# unicorder-temp-mk-2_2.net
KiCad netlist of a schematic drawn in EAGLE
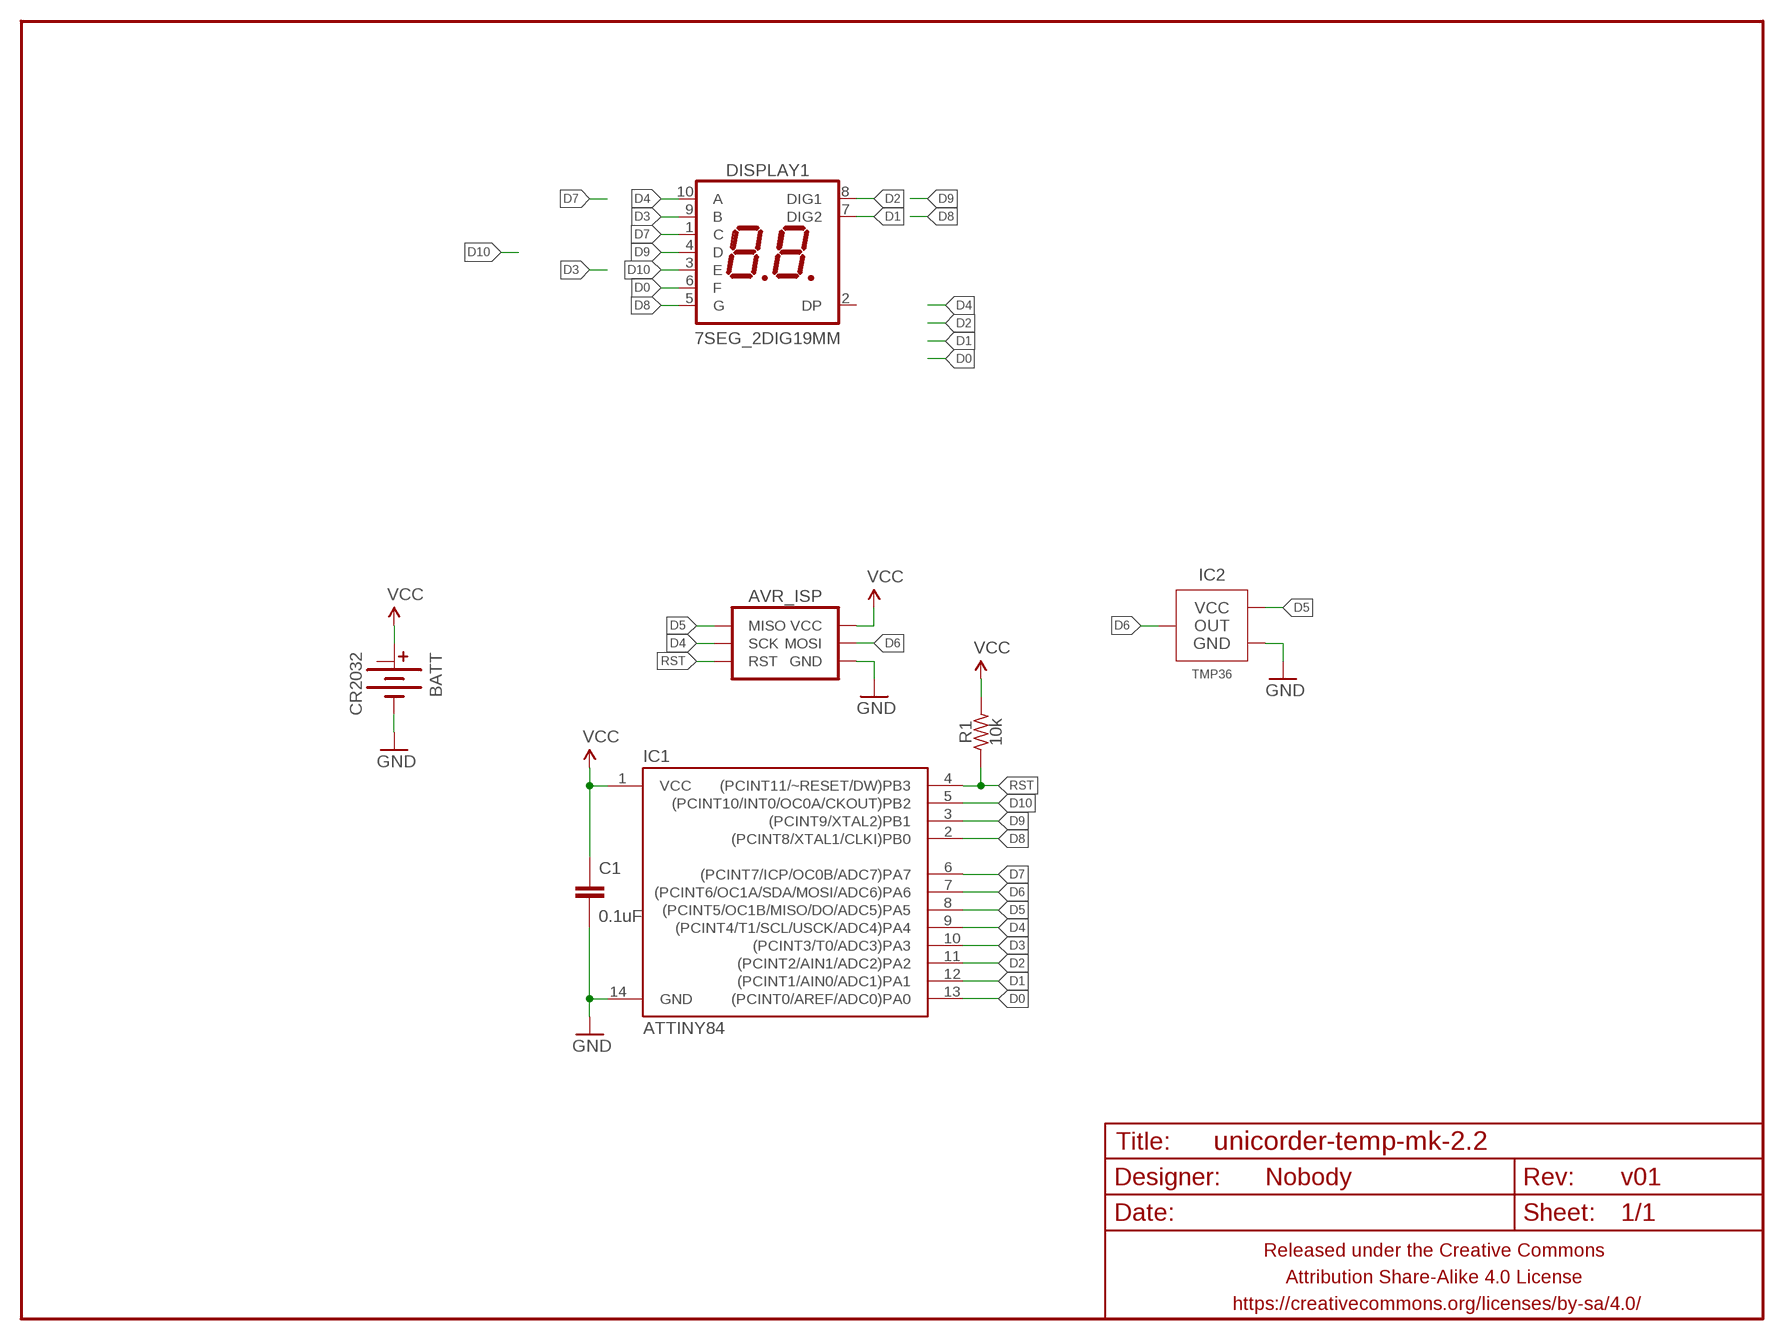
[diagram p0: schematic, sheet 1]

(export (version "E")
  (design (tool "Eeschema 10.0.6"))
  (components
    (comp (ref "AVR_ISP")
      (value "AVR_SPI_PRG_6JST-PH-VERT-PTH")
      (footprint "eagle-import:JST-6-PH-VERT-PTH")
      (libsource (lib "eagle-import") (part "AVR_SPI_PRG_6JST-PH-VERT-PTH"))
    )
    (comp (ref "BATT")
      (value "CR2032")
      (footprint "eagle-import:BATTCON_20MM_MINE")
      (libsource (lib "eagle-import") (part "BATTERY-COINCR2032_SMD"))
    )
    (comp (ref "C1")
      (value "0.1uF")
      (footprint "eagle-import:C025-024X044")
      (libsource (lib "eagle-import") (part "CAPACITOR-CERAMIC025-024X044"))
    )
    (comp (ref "DISPLAY1")
      (value "7SEG_2DIG19MM")
      (footprint "eagle-import:7SEG_2DIG_19MM")
      (libsource (lib "eagle-import") (part "7SEG_2DIG19MM"))
    )
    (comp (ref "FRAME1")
      (value "FRAME-LETTERNO_PACKAGE")
      (footprint "eagle-import:DUMMY")
      (fields (field (name "DESIGNER") "Nobody"))
      (libsource (lib "eagle-import") (part "FRAME-LETTERNO_PACKAGE"))
    )
    (comp (ref "IC1")
      (value "ATTINY84")
      (footprint "eagle-import:SO14")
      (libsource (lib "eagle-import") (part "ATTINY84"))
    )
    (comp (ref "IC2")
      (value "TMP36")
      (footprint "eagle-import:TO-92-AMMO-NARROW")
      (libsource (lib "eagle-import") (part "TMP36TO-92-NARROW"))
    )
    (comp (ref "R1")
      (value "10k")
      (footprint "eagle-import:RESISTOR-AXIAL-PTH-7.62MM")
      (libsource (lib "eagle-import") (part "RESISTORPTH-AXIAL-7.62MM"))
    )
  )
  (nets
    (net (code "1") (name "D0") (class "Default")
      (node (ref "DISPLAY1") (pin "6") (pinfunction "F_6") (pintype "passive"))
      (node (ref "IC1") (pin "13") (pinfunction "(PCINT0/AREF/ADC0)PA0_13") (pintype "bidirectional"))
    )
    (net (code "2") (name "D1") (class "Default")
      (node (ref "DISPLAY1") (pin "7") (pinfunction "DIG2_7") (pintype "passive"))
      (node (ref "IC1") (pin "12") (pinfunction "(PCINT1/AIN0/ADC1)PA1_12") (pintype "bidirectional"))
    )
    (net (code "3") (name "D2") (class "Default")
      (node (ref "DISPLAY1") (pin "8") (pinfunction "DIG1_8") (pintype "passive"))
      (node (ref "IC1") (pin "11") (pinfunction "(PCINT2/AIN1/ADC2)PA2_11") (pintype "bidirectional"))
    )
    (net (code "4") (name "D3") (class "Default")
      (node (ref "DISPLAY1") (pin "9") (pinfunction "B_9") (pintype "passive"))
      (node (ref "IC1") (pin "10") (pinfunction "(PCINT3/T0/ADC3)PA3_10") (pintype "bidirectional"))
    )
    (net (code "5") (name "D4") (class "Default")
      (node (ref "AVR_ISP") (pin "3") (pinfunction "SCK_3") (pintype "passive"))
      (node (ref "DISPLAY1") (pin "10") (pinfunction "A_10") (pintype "passive"))
      (node (ref "IC1") (pin "9") (pinfunction "(PCINT4/T1/SCL/USCK/ADC4)PA4_9") (pintype "bidirectional"))
    )
    (net (code "6") (name "D5") (class "Default")
      (node (ref "AVR_ISP") (pin "1") (pinfunction "MISO_1") (pintype "passive"))
      (node (ref "IC1") (pin "8") (pinfunction "(PCINT5/OC1B/MISO/DO/ADC5)PA5_8") (pintype "bidirectional"))
      (node (ref "IC2") (pin "1") (pinfunction "VCC_1") (pintype "bidirectional"))
    )
    (net (code "7") (name "D6") (class "Default")
      (node (ref "AVR_ISP") (pin "4") (pinfunction "MOSI_4") (pintype "passive"))
      (node (ref "IC1") (pin "7") (pinfunction "(PCINT6/OC1A/SDA/MOSI/ADC6)PA6_7") (pintype "bidirectional"))
      (node (ref "IC2") (pin "2") (pinfunction "OUT_2") (pintype "bidirectional"))
    )
    (net (code "8") (name "D7") (class "Default")
      (node (ref "DISPLAY1") (pin "1") (pinfunction "C_1") (pintype "passive"))
      (node (ref "IC1") (pin "6") (pinfunction "(PCINT7/ICP/OC0B/ADC7)PA7_6") (pintype "bidirectional"))
    )
    (net (code "9") (name "D8") (class "Default")
      (node (ref "DISPLAY1") (pin "5") (pinfunction "G_5") (pintype "passive"))
      (node (ref "IC1") (pin "2") (pinfunction "(PCINT8/XTAL1/CLKI)PB0_2") (pintype "bidirectional"))
    )
    (net (code "10") (name "D9") (class "Default")
      (node (ref "DISPLAY1") (pin "4") (pinfunction "D_4") (pintype "passive"))
      (node (ref "IC1") (pin "3") (pinfunction "(PCINT9/XTAL2)PB1_3") (pintype "bidirectional"))
    )
    (net (code "11") (name "D10") (class "Default")
      (node (ref "DISPLAY1") (pin "3") (pinfunction "E_3") (pintype "passive"))
      (node (ref "IC1") (pin "5") (pinfunction "(PCINT10/INT0/OC0A/CKOUT)PB2_5") (pintype "bidirectional"))
    )
    (net (code "12") (name "GND") (class "Default")
      (node (ref "AVR_ISP") (pin "6") (pinfunction "GND_6") (pintype "passive"))
      (node (ref "BATT") (pin "BOTTOM") (pinfunction "-_BOTTOM") (pintype "bidirectional"))
      (node (ref "C1") (pin "2") (pinfunction "2_2") (pintype "passive"))
      (node (ref "IC1") (pin "14") (pinfunction "GND_14") (pintype "bidirectional"))
      (node (ref "IC2") (pin "3") (pinfunction "GND_3") (pintype "bidirectional"))
    )
    (net (code "13") (name "RST") (class "Default")
      (node (ref "AVR_ISP") (pin "5") (pinfunction "RST_5") (pintype "passive"))
      (node (ref "IC1") (pin "4") (pinfunction "(PCINT11/~{RESET/DW})PB3_4") (pintype "bidirectional"))
      (node (ref "R1") (pin "P$1") (pinfunction "1_P$1") (pintype "passive"))
    )
    (net (code "14") (name "VCC") (class "Default")
      (node (ref "AVR_ISP") (pin "2") (pinfunction "VCC_2") (pintype "passive"))
      (node (ref "BATT") (pin "TOP@1") (pinfunction "+_TOP@1") (pintype "bidirectional"))
      (node (ref "C1") (pin "1") (pinfunction "1_1") (pintype "passive"))
      (node (ref "IC1") (pin "1") (pinfunction "VCC_1") (pintype "bidirectional"))
      (node (ref "R1") (pin "P$2") (pinfunction "2_P$2") (pintype "passive"))
    )
    (net (code "15") (name "unconnected-(BATT-+1-PadTOP@2)") (class "Default")
      (node (ref "BATT") (pin "TOP@2") (pinfunction "+1_TOP@2") (pintype "bidirectional"))
    )
    (net (code "16") (name "unconnected-(DISPLAY1-DP-Pad2)") (class "Default")
      (node (ref "DISPLAY1") (pin "2") (pinfunction "DP_2") (pintype "passive"))
    )
  )
)
